# USB_Circuitry.net
KiCad netlist of a schematic drawn in Altium Designer
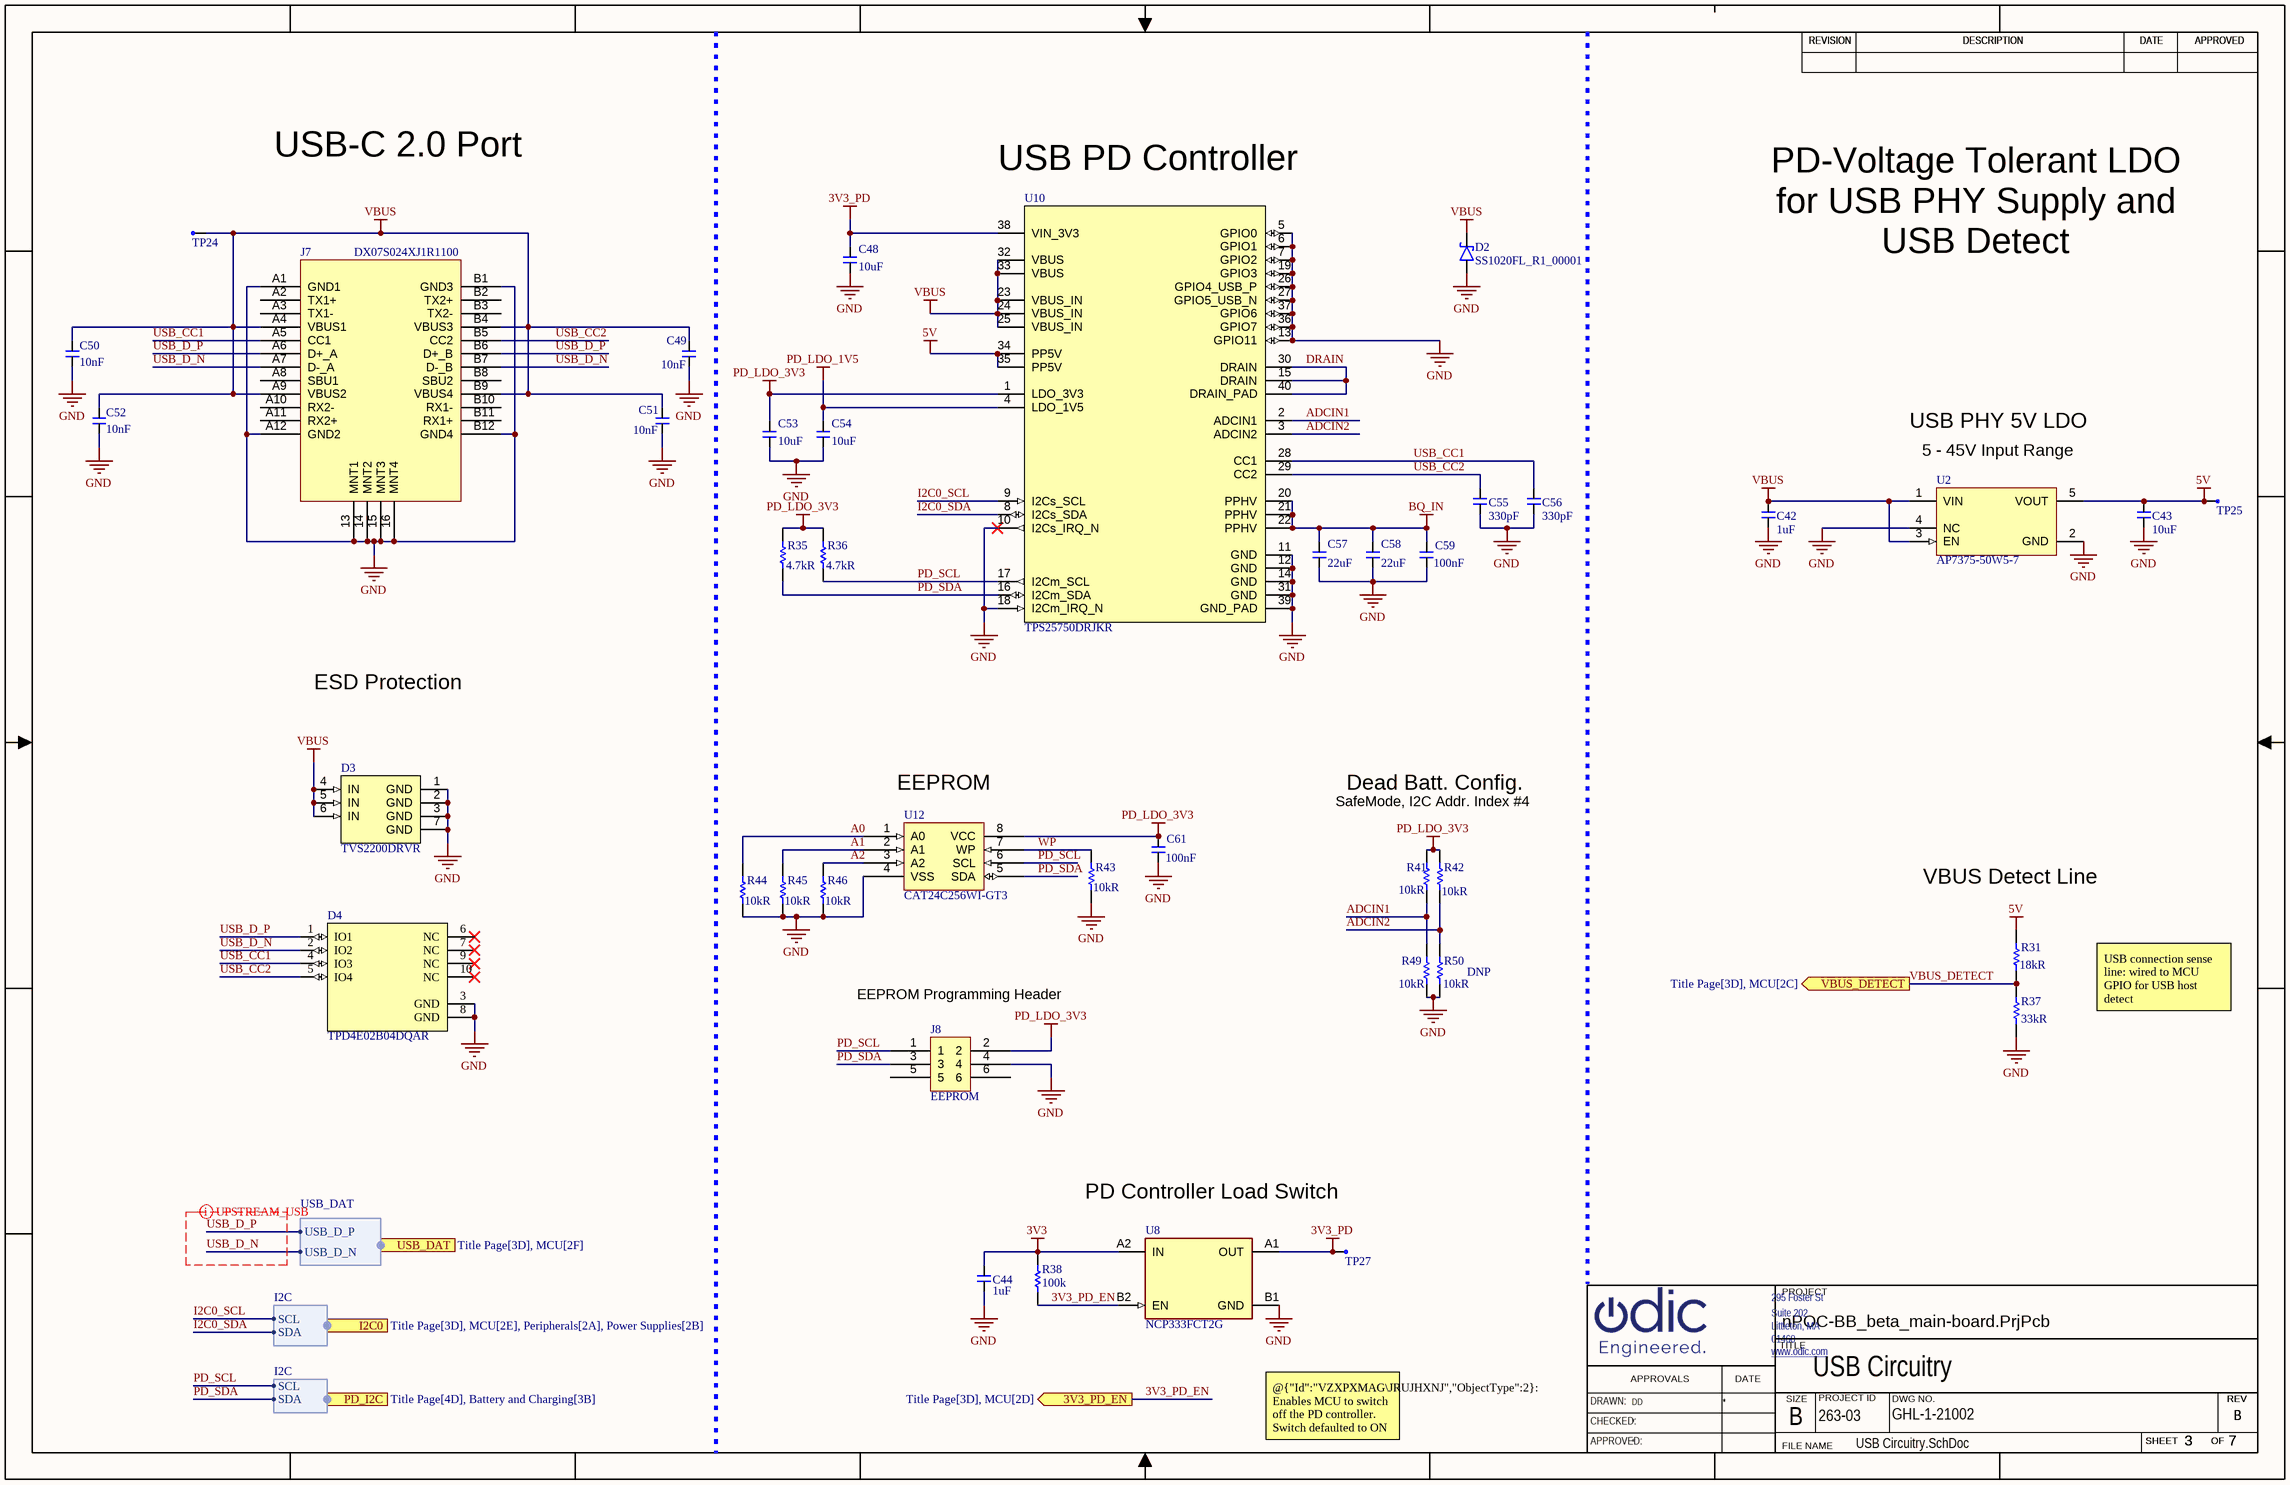
[diagram p0: USB Circuitry.SchDoc]

(export (version "E")
  (design (tool "Eeschema 10.0.6"))
  (components
    (comp (ref "C42")
      (value "1uF")
      (footprint "C0603")
      (description "Multilayer Ceramic Capacitors MLCC - SMD/SMT 1uF 50V 0603 RoHS")
      (fields (field (name "TOLERANCE") "10%"))
      (libsource (lib "Odic Inc") (part "cAP"))
    )
    (comp (ref "C43")
      (value "10uF")
      (footprint "C0402")
      (description "Ceramic capacitor SMD; 0402; 10uF; 10V; X5R; 20%")
      (fields (field (name "TOLERANCE") "20%"))
      (libsource (lib "Odic Inc") (part "cAP"))
    )
    (comp (ref "C44")
      (value "C0402_1u_6V3_10pct")
      (footprint "C0402")
      (description "Cap Ceramic 1uF 6.3V X5R 10% SMD 0402 85C Paper T/R")
      (fields (field (name "CAPACITANCE") "1uF") (field (name "TOLERANCE") "10%"))
      (libsource (lib "Odic Inc") (part "cAP"))
    )
    (comp (ref "C48")
      (value "C0402_10u_10V_20pct")
      (footprint "C0402")
      (description "Ceramic capacitor SMD; 0402; 10uF; 10V; X5R; 20%")
      (fields (field (name "CAPACITANCE") "10uF") (field (name "TOLERANCE") "20%"))
      (libsource (lib "Odic Inc") (part "cAP"))
    )
    (comp (ref "C49")
      (value "10nF")
      (footprint "C0402")
      (description "Multilayer Ceramic Capacitor, 0.01 uF, 35 V, ± 10%, X7R, 0402 [1005 Metric]")
      (fields (field (name "TOLERANCE") "10%") (field (name "Comment") "C0402_10n_35V_10pct"))
      (libsource (lib "Odic Inc") (part "cAP"))
    )
    (comp (ref "C50")
      (value "10nF")
      (footprint "C0402")
      (description "Multilayer Ceramic Capacitor, 0.01 uF, 35 V, ± 10%, X7R, 0402 [1005 Metric]")
      (fields (field (name "TOLERANCE") "10%") (field (name "Comment") "C0402_10n_35V_10pct"))
      (libsource (lib "Odic Inc") (part "cAP"))
    )
    (comp (ref "C51")
      (value "10nF")
      (footprint "C0402")
      (description "Multilayer Ceramic Capacitor, 0.01 uF, 35 V, ± 10%, X7R, 0402 [1005 Metric]")
      (fields (field (name "TOLERANCE") "10%") (field (name "Comment") "C0402_10n_35V_10pct"))
      (libsource (lib "Odic Inc") (part "cAP"))
    )
    (comp (ref "C52")
      (value "10nF")
      (footprint "C0402")
      (description "Multilayer Ceramic Capacitor, 0.01 uF, 35 V, ± 10%, X7R, 0402 [1005 Metric]")
      (fields (field (name "TOLERANCE") "10%") (field (name "Comment") "C0402_10n_35V_10pct"))
      (libsource (lib "Odic Inc") (part "cAP"))
    )
    (comp (ref "C53")
      (value "C0402_10u_10V_20pct")
      (footprint "C0402")
      (description "Ceramic capacitor SMD; 0402; 10uF; 10V; X5R; 20%")
      (fields (field (name "CAPACITANCE") "10uF") (field (name "TOLERANCE") "20%"))
      (libsource (lib "Odic Inc") (part "cAP"))
    )
    (comp (ref "C54")
      (value "C0402_10u_10V_20pct")
      (footprint "C0402")
      (description "Ceramic capacitor SMD; 0402; 10uF; 10V; X5R; 20%")
      (fields (field (name "CAPACITANCE") "10uF") (field (name "TOLERANCE") "20%"))
      (libsource (lib "Odic Inc") (part "cAP"))
    )
    (comp (ref "C55")
      (value "330pF")
      (footprint "C0402")
      (description "0402 330 pF 50 V ±5% Tolerance C0G SMT Multilayer Ceramic Capacitor")
      (fields (field (name "VOLTAGE") "50V") (field (name "TOLERANCE") "5%"))
      (libsource (lib "Odic Inc") (part "cAP"))
    )
    (comp (ref "C56")
      (value "330pF")
      (footprint "C0402")
      (description "0402 330 pF 50 V ±5% Tolerance C0G SMT Multilayer Ceramic Capacitor")
      (fields (field (name "VOLTAGE") "50V") (field (name "TOLERANCE") "5%"))
      (libsource (lib "Odic Inc") (part "cAP"))
    )
    (comp (ref "C57")
      (value "C0805_22u_25V_20pct")
      (footprint "c0805")
      (description "Multilayer Ceramic Capacitor, 22 uF, 25 V, ± 20%, X5R, 0805 [2012 Metric]")
      (fields (field (name "CAPACITANCE") "22uF"))
      (libsource (lib "Odic Inc") (part "cAP"))
    )
    (comp (ref "C58")
      (value "C0805_22u_25V_20pct")
      (footprint "c0805")
      (description "Multilayer Ceramic Capacitor, 22 uF, 25 V, ± 20%, X5R, 0805 [2012 Metric]")
      (fields (field (name "CAPACITANCE") "22uF"))
      (libsource (lib "Odic Inc") (part "cAP"))
    )
    (comp (ref "C59")
      (value "C0402_0u1_25V_10pct")
      (footprint "C0402")
      (description "Cap Ceramic 0.1uF 25V X5R 10% Pad SMD 0402 Multi Layer Ceramic Capacitor (MLCC)")
      (fields
        (field (name "VOLTAGE") "25V")
        (field (name "TOLERANCE") "10%")
        (field (name "CAPACITANCE") "100nF")
      )
      (libsource (lib "Odic Inc") (part "cAP"))
    )
    (comp (ref "C61")
      (value "C0402_0u1_25V_10pct")
      (footprint "C0402")
      (description "Cap Ceramic 0.1uF 25V X5R 10% Pad SMD 0402 Multi Layer Ceramic Capacitor (MLCC)")
      (fields
        (field (name "VOLTAGE") "25V")
        (field (name "TOLERANCE") "10%")
        (field (name "CAPACITANCE") "100nF")
      )
      (libsource (lib "Odic Inc") (part "cAP"))
    )
    (comp (ref "D2")
      (value "SS1020FL_R1_00001")
      (footprint "sod-123fl_AK")
      (description "Diode Schottky 20V 1A 2-Pin SOD-123FL T/R")
      (libsource (lib "Odic Inc") (part "Schottky"))
    )
    (comp (ref "D3")
      (value "TVS2200DRVR")
      (footprint "dfn7_2x2_p65mm")
      (description "22-V flat-clamp surge protection device 6-WSON -40 to 125")
      (libsource (lib "Odic Inc") (part "TVS2200DRVR-sym"))
    )
    (comp (ref "D4")
      (value "TPD4E02B04DQAR")
      (footprint "dfn10_1p1x2p6_p5mm")
      (description "Quad 0.25-pF, ±3.6-V, ±12-kV ESD protection diode for USB 3.0, HDMI 2.0 & High Speed Signals")
      (libsource (lib "Odic Inc") (part "TPD4E02B04DQAR-sym"))
    )
    (comp (ref "J7")
      (value "DX07S024XJ1R1100")
      (footprint "USB_JAE_DX07S024XJ1R1100")
      (libsource (lib "Odic Inc") (part "DX07S024XJ1R1100-symbol-1"))
    )
    (comp (ref "J8")
      (value "EEPROM")
      (footprint "tc2030-mcp-nl")
      (description "6 Pin Tag-Connect Header Footprint. Pads.")
      (libsource (lib "Odic Inc") (part "TC2030-FP-Symbol-1"))
    )
    (comp (ref "R31")
      (value "18kR")
      (footprint "R0402")
      (description "SMD Chip Resistor, 18 kOhm, ± 1%, 63 mW, 0402 [1005 Metric], Thick Film, General Purpose")
      (fields (field (name "TOLERANCE") "1%") (field (name "Comment") "R0402_18k_1pct"))
      (libsource (lib "Odic Inc") (part "RES"))
    )
    (comp (ref "R35")
      (value "R0402_4k7_1pct")
      (footprint "R0402")
      (description "RES 4.7K OHM 1% 1/16W 0402")
      (fields (field (name "TOLERANCE") "1%") (field (name "RESISTANCE") "4.7kR"))
      (libsource (lib "Odic Inc") (part "RES"))
    )
    (comp (ref "R36")
      (value "R0402_4k7_1pct")
      (footprint "R0402")
      (description "RES 4.7K OHM 1% 1/16W 0402")
      (fields (field (name "TOLERANCE") "1%") (field (name "RESISTANCE") "4.7kR"))
      (libsource (lib "Odic Inc") (part "RES"))
    )
    (comp (ref "R37")
      (value "R0402_33k_1pct")
      (footprint "R0402")
      (description "Res Thick Film 0402 33K Ohm 1% 0.063W(1/16W) ±100ppm/C Pad SMD T/R")
      (fields (field (name "TOLERANCE") "1%") (field (name "RESISTANCE") "33kR"))
      (libsource (lib "Odic Inc") (part "RES"))
    )
    (comp (ref "R38")
      (value "100k")
      (footprint "R0402")
      (description "Res General Purpose Thick Film 0402 100K Ohm 1% 1/16W ±100ppm/°C Molded SMD Paper T/R")
      (fields (field (name "TOLERANCE") "1%"))
      (libsource (lib "Odic Inc") (part "RES"))
    )
    (comp (ref "R41")
      (value "R0402_10k_1pct")
      (footprint "R0402")
      (description "Res Thick Film 0402 10K Ohm 1% 1/16W ±100ppm/°C Molded SMD SMD T/R")
      (fields (field (name "RESISTANCE") "10kR") (field (name "TOLERANCE") "1%"))
      (libsource (lib "Odic Inc") (part "RES"))
    )
    (comp (ref "R42")
      (value "R0402_10k_1pct")
      (footprint "R0402")
      (description "Res Thick Film 0402 10K Ohm 1% 1/16W ±100ppm/°C Molded SMD SMD T/R")
      (fields (field (name "RESISTANCE") "10kR") (field (name "TOLERANCE") "1%"))
      (libsource (lib "Odic Inc") (part "RES"))
    )
    (comp (ref "R43")
      (value "R0402_10k_1pct")
      (footprint "R0402")
      (description "Res Thick Film 0402 10K Ohm 1% 1/16W ±100ppm/°C Molded SMD SMD T/R")
      (fields (field (name "RESISTANCE") "10kR") (field (name "TOLERANCE") "1%"))
      (libsource (lib "Odic Inc") (part "RES"))
    )
    (comp (ref "R44")
      (value "R0402_10k_1pct")
      (footprint "R0402")
      (description "Res Thick Film 0402 10K Ohm 1% 1/16W ±100ppm/°C Molded SMD SMD T/R")
      (fields (field (name "RESISTANCE") "10kR") (field (name "TOLERANCE") "1%"))
      (libsource (lib "Odic Inc") (part "RES"))
    )
    (comp (ref "R45")
      (value "R0402_10k_1pct")
      (footprint "R0402")
      (description "Res Thick Film 0402 10K Ohm 1% 1/16W ±100ppm/°C Molded SMD SMD T/R")
      (fields (field (name "RESISTANCE") "10kR") (field (name "TOLERANCE") "1%"))
      (libsource (lib "Odic Inc") (part "RES"))
    )
    (comp (ref "R46")
      (value "R0402_10k_1pct")
      (footprint "R0402")
      (description "Res Thick Film 0402 10K Ohm 1% 1/16W ±100ppm/°C Molded SMD SMD T/R")
      (fields (field (name "RESISTANCE") "10kR") (field (name "TOLERANCE") "1%"))
      (libsource (lib "Odic Inc") (part "RES"))
    )
    (comp (ref "R49")
      (value "R0402_10k_1pct")
      (footprint "R0402")
      (description "Res Thick Film 0402 10K Ohm 1% 1/16W ±100ppm/°C Molded SMD SMD T/R")
      (fields (field (name "RESISTANCE") "10kR") (field (name "TOLERANCE") "1%"))
      (libsource (lib "Odic Inc") (part "RES"))
    )
    (comp (ref "R50")
      (value "R0402_10k_1pct")
      (footprint "R0402")
      (description "Res Thick Film 0402 10K Ohm 1% 1/16W ±100ppm/°C Molded SMD SMD T/R")
      (fields
        (field (name "RESISTANCE") "10kR")
        (field (name "TOLERANCE") "1%")
        (field (name "INSTALL") "DNP")
      )
      (libsource (lib "Odic Inc") (part "RES"))
    )
    (comp (ref "TP24")
      (value "TPC30")
      (footprint "tpc30")
      (description "Test Point Circle 30")
      (libsource (lib "Odic Inc") (part "TPC"))
    )
    (comp (ref "TP25")
      (value "TPC30")
      (footprint "tpc30")
      (description "Test Point Circle 30")
      (libsource (lib "Odic Inc") (part "TPC"))
    )
    (comp (ref "TP27")
      (value "TPC30")
      (footprint "tpc30")
      (description "Test Point Circle 30")
      (libsource (lib "Odic Inc") (part "TPC"))
    )
    (comp (ref "U2")
      (value "AP7375-50W5-7")
      (footprint "SOT25")
      (description "Fixed 5V LDO Voltage Regulators LDO CMOS LowCurr SOT23 TR 3K")
      (libsource (lib "Odic Inc") (part "0611416dd6b6fc2280b1ddb1fddec67"))
    )
    (comp (ref "U8")
      (value "NCP333FCT2G")
      (footprint "bga4_p743xp743_p4mm")
      (description "IC LOAD SWITCH W/DIS 1.5A 4WLCSP")
      (libsource (lib "Odic Inc") (part "97019fd276bc7644be76e1f711e9589"))
    )
    (comp (ref "U10")
      (value "TPS25750DRJKR")
      (footprint "qfn40_6x4_p4mm-RJK0038B")
      (description "Highly integrated USB Type-C® and USB PD controller with pre-configured GUI 38-WQFN -40 to 125")
      (libsource (lib "Odic Inc") (part "TPS25750DRJKR-Symbol-1"))
    )
    (comp (ref "U12")
      (value "CAT24C256WI-GT3")
      (footprint "SO8")
      (description "IC EEPROM 256KBIT 400KHZ 8SOIC")
      (libsource (lib "Odic Inc") (part "CAT24C256WI-GT3-Symbol-1"))
    )
  )
  (nets
    (net (code "3") (name "/3V3_PD_EN") (class "Default")
      (node (ref "R38") (pin "1") (pinfunction "1_1") (pintype "passive"))
      (node (ref "U8") (pin "B2") (pinfunction "EN_B2") (pintype "input"))
    )
    (net (code "4") (name "/A0") (class "Default")
      (node (ref "R44") (pin "2") (pinfunction "2_2") (pintype "passive"))
      (node (ref "U12") (pin "1") (pinfunction "A0_1") (pintype "input"))
    )
    (net (code "5") (name "/A1") (class "Default")
      (node (ref "R45") (pin "2") (pinfunction "2_2") (pintype "passive"))
      (node (ref "U12") (pin "2") (pinfunction "A1_2") (pintype "input"))
    )
    (net (code "6") (name "/A2") (class "Default")
      (node (ref "R46") (pin "2") (pinfunction "2_2") (pintype "passive"))
      (node (ref "U12") (pin "3") (pinfunction "A2_3") (pintype "input"))
    )
    (net (code "7") (name "/ADCIN1") (class "Default")
      (node (ref "R41") (pin "1") (pinfunction "1_1") (pintype "passive"))
      (node (ref "R49") (pin "2") (pinfunction "2_2") (pintype "passive"))
      (node (ref "U10") (pin "2") (pinfunction "ADCIN1_2") (pintype "passive"))
    )
    (net (code "8") (name "/ADCIN2") (class "Default")
      (node (ref "R42") (pin "1") (pinfunction "1_1") (pintype "passive"))
      (node (ref "R50") (pin "2") (pinfunction "2_2") (pintype "passive"))
      (node (ref "U10") (pin "3") (pinfunction "ADCIN2_3") (pintype "passive"))
    )
    (net (code "9") (name "/DRAIN") (class "Default")
      (node (ref "U10") (pin "15") (pinfunction "DRAIN_15") (pintype "passive"))
      (node (ref "U10") (pin "30") (pinfunction "DRAIN_30") (pintype "passive"))
      (node (ref "U10") (pin "40") (pinfunction "DRAIN_PAD_40") (pintype "passive"))
    )
    (net (code "10") (name "/I2C0_SCL") (class "Default")
      (node (ref "U10") (pin "9") (pinfunction "I2Cs_SCL_9") (pintype "input"))
    )
    (net (code "11") (name "/I2C0_SDA") (class "Default")
      (node (ref "U10") (pin "8") (pinfunction "I2Cs_SDA_8") (pintype "bidirectional"))
    )
    (net (code "12") (name "/PD_SCL") (class "Default")
      (node (ref "J8") (pin "1") (pinfunction "1_1") (pintype "passive"))
      (node (ref "R36") (pin "1") (pinfunction "1_1") (pintype "passive"))
      (node (ref "U10") (pin "17") (pinfunction "I2Cm_SCL_17") (pintype "output"))
      (node (ref "U12") (pin "6") (pinfunction "SCL_6") (pintype "input"))
    )
    (net (code "13") (name "/PD_SDA") (class "Default")
      (node (ref "J8") (pin "3") (pinfunction "3_3") (pintype "passive"))
      (node (ref "R35") (pin "1") (pinfunction "1_1") (pintype "passive"))
      (node (ref "U10") (pin "16") (pinfunction "I2Cm_SDA_16") (pintype "bidirectional"))
      (node (ref "U12") (pin "5") (pinfunction "SDA_5") (pintype "bidirectional"))
    )
    (net (code "14") (name "/USB_CC1") (class "Default")
      (node (ref "C56") (pin "2") (pinfunction "2_2") (pintype "passive"))
      (node (ref "D4") (pin "4") (pinfunction "IO3_4") (pintype "bidirectional"))
      (node (ref "J7") (pin "A5") (pinfunction "CC1_A5") (pintype "passive"))
      (node (ref "U10") (pin "28") (pinfunction "CC1_28") (pintype "passive"))
    )
    (net (code "15") (name "/USB_CC2") (class "Default")
      (node (ref "C55") (pin "2") (pinfunction "2_2") (pintype "passive"))
      (node (ref "D4") (pin "5") (pinfunction "IO4_5") (pintype "bidirectional"))
      (node (ref "J7") (pin "B5") (pinfunction "CC2_B5") (pintype "passive"))
      (node (ref "U10") (pin "29") (pinfunction "CC2_29") (pintype "passive"))
    )
    (net (code "16") (name "/USB_D_N") (class "Default")
      (node (ref "D4") (pin "2") (pinfunction "IO2_2") (pintype "bidirectional"))
      (node (ref "J7") (pin "A7") (pinfunction "D-_A_A7") (pintype "passive"))
      (node (ref "J7") (pin "B7") (pinfunction "D-_B_B7") (pintype "passive"))
    )
    (net (code "17") (name "/USB_D_P") (class "Default")
      (node (ref "D4") (pin "1") (pinfunction "IO1_1") (pintype "bidirectional"))
      (node (ref "J7") (pin "A6") (pinfunction "D+_A_A6") (pintype "passive"))
      (node (ref "J7") (pin "B6") (pinfunction "D+_B_B6") (pintype "passive"))
    )
    (net (code "18") (name "/VBUS_DETECT") (class "Default")
      (node (ref "R31") (pin "1") (pinfunction "1_1") (pintype "passive"))
      (node (ref "R37") (pin "2") (pinfunction "2_2") (pintype "passive"))
    )
    (net (code "19") (name "/WP") (class "Default")
      (node (ref "R43") (pin "2") (pinfunction "2_2") (pintype "passive"))
      (node (ref "U12") (pin "7") (pinfunction "WP_7") (pintype "input"))
    )
    (net (code "22") (name "3V3") (class "Default")
      (node (ref "C44") (pin "2") (pinfunction "2_2") (pintype "passive"))
      (node (ref "R38") (pin "2") (pinfunction "2_2") (pintype "passive"))
      (node (ref "U8") (pin "A2") (pinfunction "IN_A2") (pintype "power_in"))
    )
    (net (code "23") (name "3V3_PD") (class "Default")
      (node (ref "C48") (pin "2") (pinfunction "2_2") (pintype "passive"))
      (node (ref "TP27") (pin "1") (pinfunction "1_1") (pintype "passive"))
      (node (ref "U10") (pin "38") (pinfunction "VIN_3V3_38") (pintype "power_in"))
      (node (ref "U8") (pin "A1") (pinfunction "OUT_A1") (pintype "power_in"))
    )
    (net (code "24") (name "5V") (class "Default")
      (node (ref "C43") (pin "2") (pinfunction "2_2") (pintype "passive"))
      (node (ref "R31") (pin "2") (pinfunction "2_2") (pintype "passive"))
      (node (ref "TP25") (pin "1") (pinfunction "1_1") (pintype "passive"))
      (node (ref "U10") (pin "34") (pinfunction "PP5V_34") (pintype "power_in"))
      (node (ref "U10") (pin "35") (pinfunction "PP5V_35") (pintype "power_in"))
      (node (ref "U2") (pin "5") (pinfunction "VOUT_5") (pintype "power_in"))
    )
    (net (code "25") (name "BQ_IN") (class "Default")
      (node (ref "C57") (pin "2") (pinfunction "2_2") (pintype "passive"))
      (node (ref "C58") (pin "2") (pinfunction "2_2") (pintype "passive"))
      (node (ref "C59") (pin "2") (pinfunction "2_2") (pintype "passive"))
      (node (ref "U10") (pin "20") (pinfunction "PPHV_20") (pintype "passive"))
      (node (ref "U10") (pin "21") (pinfunction "PPHV_21") (pintype "passive"))
      (node (ref "U10") (pin "22") (pinfunction "PPHV_22") (pintype "passive"))
    )
    (net (code "26") (name "GND") (class "Default")
      (node (ref "C42") (pin "1") (pinfunction "1_1") (pintype "passive"))
      (node (ref "C43") (pin "1") (pinfunction "1_1") (pintype "passive"))
      (node (ref "C44") (pin "1") (pinfunction "1_1") (pintype "passive"))
      (node (ref "C48") (pin "1") (pinfunction "1_1") (pintype "passive"))
      (node (ref "C49") (pin "1") (pinfunction "1_1") (pintype "passive"))
      (node (ref "C50") (pin "1") (pinfunction "1_1") (pintype "passive"))
      (node (ref "C51") (pin "1") (pinfunction "1_1") (pintype "passive"))
      (node (ref "C52") (pin "1") (pinfunction "1_1") (pintype "passive"))
      (node (ref "C53") (pin "1") (pinfunction "1_1") (pintype "passive"))
      (node (ref "C54") (pin "1") (pinfunction "1_1") (pintype "passive"))
      (node (ref "C55") (pin "1") (pinfunction "1_1") (pintype "passive"))
      (node (ref "C56") (pin "1") (pinfunction "1_1") (pintype "passive"))
      (node (ref "C57") (pin "1") (pinfunction "1_1") (pintype "passive"))
      (node (ref "C58") (pin "1") (pinfunction "1_1") (pintype "passive"))
      (node (ref "C59") (pin "1") (pinfunction "1_1") (pintype "passive"))
      (node (ref "C61") (pin "1") (pinfunction "1_1") (pintype "passive"))
      (node (ref "D2") (pin "A") (pinfunction "A_A") (pintype "passive"))
      (node (ref "D3") (pin "1") (pinfunction "GND_1") (pintype "power_in"))
      (node (ref "D3") (pin "2") (pinfunction "GND_2") (pintype "power_in"))
      (node (ref "D3") (pin "3") (pinfunction "GND_3") (pintype "power_in"))
      (node (ref "D3") (pin "7") (pinfunction "GND_7") (pintype "power_in"))
      (node (ref "D4") (pin "3") (pinfunction "GND_3") (pintype "power_in"))
      (node (ref "D4") (pin "8") (pinfunction "GND_8") (pintype "power_in"))
      (node (ref "J7") (pin "13") (pinfunction "MNT1_13") (pintype "passive"))
      (node (ref "J7") (pin "14") (pinfunction "MNT2_14") (pintype "passive"))
      (node (ref "J7") (pin "15") (pinfunction "MNT3_15") (pintype "passive"))
      (node (ref "J7") (pin "16") (pinfunction "MNT4_16") (pintype "passive"))
      (node (ref "J7") (pin "A1") (pinfunction "GND1_A1") (pintype "passive"))
      (node (ref "J7") (pin "A12") (pinfunction "GND2_A12") (pintype "passive"))
      (node (ref "J7") (pin "B1") (pinfunction "GND3_B1") (pintype "passive"))
      (node (ref "J7") (pin "B12") (pinfunction "GND4_B12") (pintype "passive"))
      (node (ref "J8") (pin "4") (pinfunction "4_4") (pintype "passive"))
      (node (ref "R37") (pin "1") (pinfunction "1_1") (pintype "passive"))
      (node (ref "R43") (pin "1") (pinfunction "1_1") (pintype "passive"))
      (node (ref "R44") (pin "1") (pinfunction "1_1") (pintype "passive"))
      (node (ref "R45") (pin "1") (pinfunction "1_1") (pintype "passive"))
      (node (ref "R46") (pin "1") (pinfunction "1_1") (pintype "passive"))
      (node (ref "R49") (pin "1") (pinfunction "1_1") (pintype "passive"))
      (node (ref "R50") (pin "1") (pinfunction "1_1") (pintype "passive"))
      (node (ref "U10") (pin "10") (pinfunction "I2Cs_IRQ_N_10") (pintype "output"))
      (node (ref "U10") (pin "11") (pinfunction "GND_11") (pintype "power_in"))
      (node (ref "U10") (pin "12") (pinfunction "GND_12") (pintype "power_in"))
      (node (ref "U10") (pin "13") (pinfunction "GPIO11_13") (pintype "bidirectional"))
      (node (ref "U10") (pin "14") (pinfunction "GND_14") (pintype "power_in"))
      (node (ref "U10") (pin "18") (pinfunction "I2Cm_IRQ_N_18") (pintype "input"))
      (node (ref "U10") (pin "19") (pinfunction "GPIO3_19") (pintype "bidirectional"))
      (node (ref "U10") (pin "26") (pinfunction "GPIO4_USB_P_26") (pintype "bidirectional"))
      (node (ref "U10") (pin "27") (pinfunction "GPIO5_USB_N_27") (pintype "bidirectional"))
      (node (ref "U10") (pin "31") (pinfunction "GND_31") (pintype "power_in"))
      (node (ref "U10") (pin "36") (pinfunction "GPIO7_36") (pintype "bidirectional"))
      (node (ref "U10") (pin "37") (pinfunction "GPIO6_37") (pintype "bidirectional"))
      (node (ref "U10") (pin "39") (pinfunction "GND_PAD_39") (pintype "power_in"))
      (node (ref "U10") (pin "5") (pinfunction "GPIO0_5") (pintype "bidirectional"))
      (node (ref "U10") (pin "6") (pinfunction "GPIO1_6") (pintype "bidirectional"))
      (node (ref "U10") (pin "7") (pinfunction "GPIO2_7") (pintype "bidirectional"))
      (node (ref "U12") (pin "4") (pinfunction "VSS_4") (pintype "passive"))
      (node (ref "U2") (pin "2") (pinfunction "GND_2") (pintype "power_in"))
      (node (ref "U2") (pin "4") (pinfunction "NC_4") (pintype "passive"))
      (node (ref "U8") (pin "B1") (pinfunction "GND_B1") (pintype "power_in"))
    )
    (net (code "27") (name "PD_LDO_1V5") (class "Default")
      (node (ref "C54") (pin "2") (pinfunction "2_2") (pintype "passive"))
      (node (ref "U10") (pin "4") (pinfunction "LDO_1V5_4") (pintype "passive"))
    )
    (net (code "28") (name "PD_LDO_3V3") (class "Default")
      (node (ref "C53") (pin "2") (pinfunction "2_2") (pintype "passive"))
      (node (ref "C61") (pin "2") (pinfunction "2_2") (pintype "passive"))
      (node (ref "J8") (pin "2") (pinfunction "2_2") (pintype "passive"))
      (node (ref "R35") (pin "2") (pinfunction "2_2") (pintype "passive"))
      (node (ref "R36") (pin "2") (pinfunction "2_2") (pintype "passive"))
      (node (ref "R41") (pin "2") (pinfunction "2_2") (pintype "passive"))
      (node (ref "R42") (pin "2") (pinfunction "2_2") (pintype "passive"))
      (node (ref "U10") (pin "1") (pinfunction "LDO_3V3_1") (pintype "passive"))
      (node (ref "U12") (pin "8") (pinfunction "VCC_8") (pintype "passive"))
    )
    (net (code "29") (name "VBUS") (class "Default")
      (node (ref "C42") (pin "2") (pinfunction "2_2") (pintype "passive"))
      (node (ref "C49") (pin "2") (pinfunction "2_2") (pintype "passive"))
      (node (ref "C50") (pin "2") (pinfunction "2_2") (pintype "passive"))
      (node (ref "C51") (pin "2") (pinfunction "2_2") (pintype "passive"))
      (node (ref "C52") (pin "2") (pinfunction "2_2") (pintype "passive"))
      (node (ref "D2") (pin "K") (pinfunction "K_K") (pintype "passive"))
      (node (ref "D3") (pin "4") (pinfunction "IN_4") (pintype "input"))
      (node (ref "D3") (pin "5") (pinfunction "IN_5") (pintype "input"))
      (node (ref "D3") (pin "6") (pinfunction "IN_6") (pintype "input"))
      (node (ref "J7") (pin "A4") (pinfunction "VBUS1_A4") (pintype "passive"))
      (node (ref "J7") (pin "A9") (pinfunction "VBUS2_A9") (pintype "passive"))
      (node (ref "J7") (pin "B4") (pinfunction "VBUS3_B4") (pintype "passive"))
      (node (ref "J7") (pin "B9") (pinfunction "VBUS4_B9") (pintype "passive"))
      (node (ref "TP24") (pin "1") (pinfunction "1_1") (pintype "passive"))
      (node (ref "U10") (pin "23") (pinfunction "VBUS_IN_23") (pintype "power_in"))
      (node (ref "U10") (pin "24") (pinfunction "VBUS_IN_24") (pintype "power_in"))
      (node (ref "U10") (pin "25") (pinfunction "VBUS_IN_25") (pintype "power_in"))
      (node (ref "U10") (pin "32") (pinfunction "VBUS_32") (pintype "power_in"))
      (node (ref "U10") (pin "33") (pinfunction "VBUS_33") (pintype "power_in"))
      (node (ref "U2") (pin "1") (pinfunction "VIN_1") (pintype "power_in"))
      (node (ref "U2") (pin "3") (pinfunction "EN_3") (pintype "input"))
    )
    (net (code "30") (name "unconnected-(D4-NC-Pad6)") (class "Default")
      (node (ref "D4") (pin "6") (pinfunction "NC_6") (pintype "passive+no_connect"))
    )
    (net (code "31") (name "unconnected-(D4-NC-Pad7)") (class "Default")
      (node (ref "D4") (pin "7") (pinfunction "NC_7") (pintype "passive+no_connect"))
    )
    (net (code "32") (name "unconnected-(D4-NC-Pad9)") (class "Default")
      (node (ref "D4") (pin "9") (pinfunction "NC_9") (pintype "passive+no_connect"))
    )
    (net (code "33") (name "unconnected-(D4-NC-Pad10)") (class "Default")
      (node (ref "D4") (pin "10") (pinfunction "NC_10") (pintype "passive+no_connect"))
    )
    (net (code "34") (name "unconnected-(J7-RX1+-PadB11)") (class "Default")
      (node (ref "J7") (pin "B11") (pinfunction "RX1+_B11") (pintype "passive"))
    )
    (net (code "35") (name "unconnected-(J7-RX1--PadB10)") (class "Default")
      (node (ref "J7") (pin "B10") (pinfunction "RX1-_B10") (pintype "passive"))
    )
    (net (code "36") (name "unconnected-(J7-RX2+-PadA11)") (class "Default")
      (node (ref "J7") (pin "A11") (pinfunction "RX2+_A11") (pintype "passive"))
    )
    (net (code "37") (name "unconnected-(J7-RX2--PadA10)") (class "Default")
      (node (ref "J7") (pin "A10") (pinfunction "RX2-_A10") (pintype "passive"))
    )
    (net (code "38") (name "unconnected-(J7-SBU1-PadA8)") (class "Default")
      (node (ref "J7") (pin "A8") (pinfunction "SBU1_A8") (pintype "passive"))
    )
    (net (code "39") (name "unconnected-(J7-SBU2-PadB8)") (class "Default")
      (node (ref "J7") (pin "B8") (pinfunction "SBU2_B8") (pintype "passive"))
    )
    (net (code "40") (name "unconnected-(J7-TX1+-PadA2)") (class "Default")
      (node (ref "J7") (pin "A2") (pinfunction "TX1+_A2") (pintype "passive"))
    )
    (net (code "41") (name "unconnected-(J7-TX1--PadA3)") (class "Default")
      (node (ref "J7") (pin "A3") (pinfunction "TX1-_A3") (pintype "passive"))
    )
    (net (code "42") (name "unconnected-(J7-TX2+-PadB2)") (class "Default")
      (node (ref "J7") (pin "B2") (pinfunction "TX2+_B2") (pintype "passive"))
    )
    (net (code "43") (name "unconnected-(J7-TX2--PadB3)") (class "Default")
      (node (ref "J7") (pin "B3") (pinfunction "TX2-_B3") (pintype "passive"))
    )
    (net (code "44") (name "unconnected-(J8-Pad5)") (class "Default")
      (node (ref "J8") (pin "5") (pinfunction "5_5") (pintype "passive"))
    )
    (net (code "45") (name "unconnected-(J8-Pad6)") (class "Default")
      (node (ref "J8") (pin "6") (pinfunction "6_6") (pintype "passive"))
    )
  )
)
